# schematic_v1.net
KiCad netlist of a schematic drawn in EAGLE
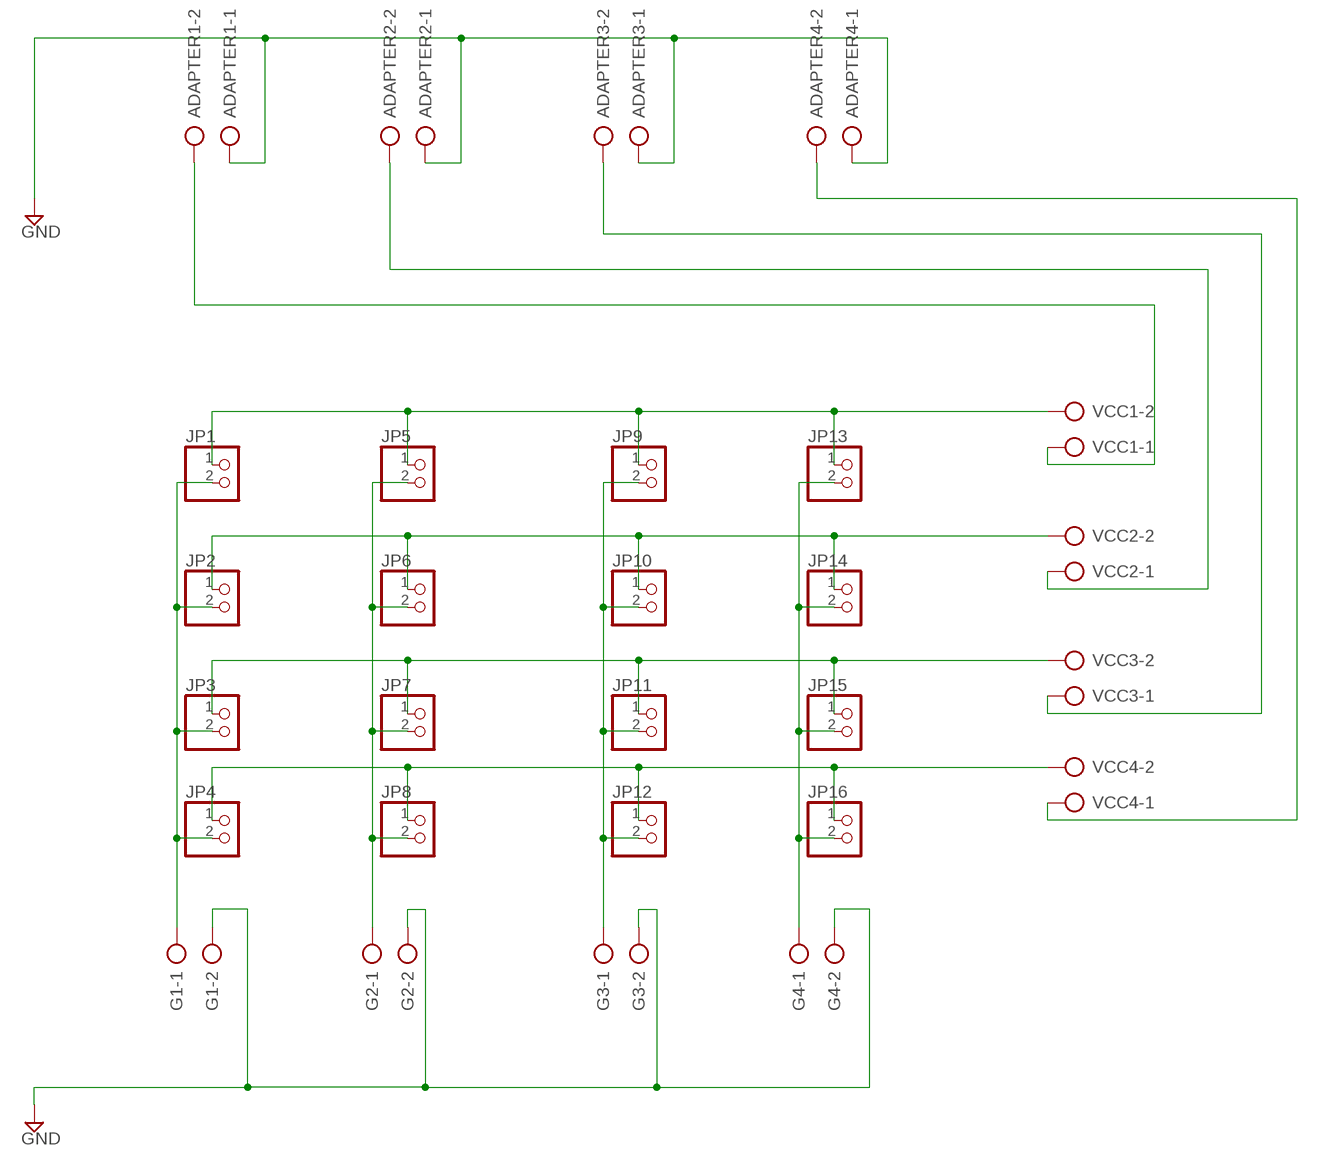
[diagram p0: schematic, sheet 1]

(export (version "E")
  (design (tool "Eeschema 10.0.6"))
  (components
    (comp (ref "ADAPTER1")
      (value "AK300/2")
      (footprint "eagle-import:AK300_2")
      (libsource (lib "eagle-import") (part "AK300/2"))
    )
    (comp (ref "ADAPTER2")
      (value "AK300/2")
      (footprint "eagle-import:AK300_2")
      (libsource (lib "eagle-import") (part "AK300/2"))
    )
    (comp (ref "ADAPTER3")
      (value "AK300/2")
      (footprint "eagle-import:AK300_2")
      (libsource (lib "eagle-import") (part "AK300/2"))
    )
    (comp (ref "ADAPTER4")
      (value "AK300/2")
      (footprint "eagle-import:AK300_2")
      (libsource (lib "eagle-import") (part "AK300/2"))
    )
    (comp (ref "G1")
      (value "AK300/2")
      (footprint "eagle-import:AK300_2")
      (libsource (lib "eagle-import") (part "AK300/2"))
    )
    (comp (ref "G2")
      (value "AK300/2")
      (footprint "eagle-import:AK300_2")
      (libsource (lib "eagle-import") (part "AK300/2"))
    )
    (comp (ref "G3")
      (value "AK300/2")
      (footprint "eagle-import:AK300_2")
      (libsource (lib "eagle-import") (part "AK300/2"))
    )
    (comp (ref "G4")
      (value "AK300/2")
      (footprint "eagle-import:AK300_2")
      (libsource (lib "eagle-import") (part "AK300/2"))
    )
    (comp (ref "JP1")
      (value "PINHD-1X2")
      (footprint "eagle-import:1X02")
      (libsource (lib "eagle-import") (part "PINHD-1X2"))
    )
    (comp (ref "JP2")
      (value "PINHD-1X2")
      (footprint "eagle-import:1X02")
      (libsource (lib "eagle-import") (part "PINHD-1X2"))
    )
    (comp (ref "JP3")
      (value "PINHD-1X2")
      (footprint "eagle-import:1X02")
      (libsource (lib "eagle-import") (part "PINHD-1X2"))
    )
    (comp (ref "JP4")
      (value "PINHD-1X2")
      (footprint "eagle-import:1X02")
      (libsource (lib "eagle-import") (part "PINHD-1X2"))
    )
    (comp (ref "JP5")
      (value "PINHD-1X2")
      (footprint "eagle-import:1X02")
      (libsource (lib "eagle-import") (part "PINHD-1X2"))
    )
    (comp (ref "JP6")
      (value "PINHD-1X2")
      (footprint "eagle-import:1X02")
      (libsource (lib "eagle-import") (part "PINHD-1X2"))
    )
    (comp (ref "JP7")
      (value "PINHD-1X2")
      (footprint "eagle-import:1X02")
      (libsource (lib "eagle-import") (part "PINHD-1X2"))
    )
    (comp (ref "JP8")
      (value "PINHD-1X2")
      (footprint "eagle-import:1X02")
      (libsource (lib "eagle-import") (part "PINHD-1X2"))
    )
    (comp (ref "JP9")
      (value "PINHD-1X2")
      (footprint "eagle-import:1X02")
      (libsource (lib "eagle-import") (part "PINHD-1X2"))
    )
    (comp (ref "JP10")
      (value "PINHD-1X2")
      (footprint "eagle-import:1X02")
      (libsource (lib "eagle-import") (part "PINHD-1X2"))
    )
    (comp (ref "JP11")
      (value "PINHD-1X2")
      (footprint "eagle-import:1X02")
      (libsource (lib "eagle-import") (part "PINHD-1X2"))
    )
    (comp (ref "JP12")
      (value "PINHD-1X2")
      (footprint "eagle-import:1X02")
      (libsource (lib "eagle-import") (part "PINHD-1X2"))
    )
    (comp (ref "JP13")
      (value "PINHD-1X2")
      (footprint "eagle-import:1X02")
      (libsource (lib "eagle-import") (part "PINHD-1X2"))
    )
    (comp (ref "JP14")
      (value "PINHD-1X2")
      (footprint "eagle-import:1X02")
      (libsource (lib "eagle-import") (part "PINHD-1X2"))
    )
    (comp (ref "JP15")
      (value "PINHD-1X2")
      (footprint "eagle-import:1X02")
      (libsource (lib "eagle-import") (part "PINHD-1X2"))
    )
    (comp (ref "JP16")
      (value "PINHD-1X2")
      (footprint "eagle-import:1X02")
      (libsource (lib "eagle-import") (part "PINHD-1X2"))
    )
    (comp (ref "VCC1")
      (value "AK300/2")
      (footprint "eagle-import:AK300_2")
      (libsource (lib "eagle-import") (part "AK300/2"))
    )
    (comp (ref "VCC2")
      (value "AK300/2")
      (footprint "eagle-import:AK300_2")
      (libsource (lib "eagle-import") (part "AK300/2"))
    )
    (comp (ref "VCC3")
      (value "AK300/2")
      (footprint "eagle-import:AK300_2")
      (libsource (lib "eagle-import") (part "AK300/2"))
    )
    (comp (ref "VCC4")
      (value "AK300/2")
      (footprint "eagle-import:AK300_2")
      (libsource (lib "eagle-import") (part "AK300/2"))
    )
  )
  (nets
    (net (code "1") (name "GND") (class "Default")
      (node (ref "ADAPTER1") (pin "1") (pinfunction "KL_1") (pintype "passive"))
      (node (ref "ADAPTER2") (pin "1") (pinfunction "KL_1") (pintype "passive"))
      (node (ref "ADAPTER3") (pin "1") (pinfunction "KL_1") (pintype "passive"))
      (node (ref "ADAPTER4") (pin "1") (pinfunction "KL_1") (pintype "passive"))
      (node (ref "G1") (pin "2") (pinfunction "KL_2") (pintype "passive"))
      (node (ref "G2") (pin "2") (pinfunction "KL_2") (pintype "passive"))
      (node (ref "G3") (pin "2") (pinfunction "KL_2") (pintype "passive"))
      (node (ref "G4") (pin "2") (pinfunction "KL_2") (pintype "passive"))
    )
    (net (code "2") (name "Net-(ADAPTER1B-KL)") (class "Default")
      (node (ref "ADAPTER1") (pin "2") (pinfunction "KL_2") (pintype "passive"))
      (node (ref "VCC1") (pin "1") (pinfunction "KL_1") (pintype "passive"))
    )
    (net (code "3") (name "Net-(ADAPTER2B-KL)") (class "Default")
      (node (ref "ADAPTER2") (pin "2") (pinfunction "KL_2") (pintype "passive"))
      (node (ref "VCC2") (pin "1") (pinfunction "KL_1") (pintype "passive"))
    )
    (net (code "4") (name "Net-(ADAPTER3B-KL)") (class "Default")
      (node (ref "ADAPTER3") (pin "2") (pinfunction "KL_2") (pintype "passive"))
      (node (ref "VCC3") (pin "1") (pinfunction "KL_1") (pintype "passive"))
    )
    (net (code "5") (name "Net-(ADAPTER4B-KL)") (class "Default")
      (node (ref "ADAPTER4") (pin "2") (pinfunction "KL_2") (pintype "passive"))
      (node (ref "VCC4") (pin "1") (pinfunction "KL_1") (pintype "passive"))
    )
    (net (code "6") (name "Net-(G1A-KL)") (class "Default")
      (node (ref "G1") (pin "1") (pinfunction "KL_1") (pintype "passive"))
      (node (ref "JP1") (pin "2") (pinfunction "2_2") (pintype "passive"))
      (node (ref "JP2") (pin "2") (pinfunction "2_2") (pintype "passive"))
      (node (ref "JP3") (pin "2") (pinfunction "2_2") (pintype "passive"))
      (node (ref "JP4") (pin "2") (pinfunction "2_2") (pintype "passive"))
    )
    (net (code "7") (name "Net-(G2A-KL)") (class "Default")
      (node (ref "G2") (pin "1") (pinfunction "KL_1") (pintype "passive"))
      (node (ref "JP5") (pin "2") (pinfunction "2_2") (pintype "passive"))
      (node (ref "JP6") (pin "2") (pinfunction "2_2") (pintype "passive"))
      (node (ref "JP7") (pin "2") (pinfunction "2_2") (pintype "passive"))
      (node (ref "JP8") (pin "2") (pinfunction "2_2") (pintype "passive"))
    )
    (net (code "8") (name "Net-(G3A-KL)") (class "Default")
      (node (ref "G3") (pin "1") (pinfunction "KL_1") (pintype "passive"))
      (node (ref "JP10") (pin "2") (pinfunction "2_2") (pintype "passive"))
      (node (ref "JP11") (pin "2") (pinfunction "2_2") (pintype "passive"))
      (node (ref "JP12") (pin "2") (pinfunction "2_2") (pintype "passive"))
      (node (ref "JP9") (pin "2") (pinfunction "2_2") (pintype "passive"))
    )
    (net (code "9") (name "Net-(G4A-KL)") (class "Default")
      (node (ref "G4") (pin "1") (pinfunction "KL_1") (pintype "passive"))
      (node (ref "JP13") (pin "2") (pinfunction "2_2") (pintype "passive"))
      (node (ref "JP14") (pin "2") (pinfunction "2_2") (pintype "passive"))
      (node (ref "JP15") (pin "2") (pinfunction "2_2") (pintype "passive"))
      (node (ref "JP16") (pin "2") (pinfunction "2_2") (pintype "passive"))
    )
    (net (code "10") (name "Net-(VCC1B-KL)") (class "Default")
      (node (ref "JP1") (pin "1") (pinfunction "1_1") (pintype "passive"))
      (node (ref "JP13") (pin "1") (pinfunction "1_1") (pintype "passive"))
      (node (ref "JP5") (pin "1") (pinfunction "1_1") (pintype "passive"))
      (node (ref "JP9") (pin "1") (pinfunction "1_1") (pintype "passive"))
      (node (ref "VCC1") (pin "2") (pinfunction "KL_2") (pintype "passive"))
    )
    (net (code "11") (name "Net-(VCC2B-KL)") (class "Default")
      (node (ref "JP10") (pin "1") (pinfunction "1_1") (pintype "passive"))
      (node (ref "JP14") (pin "1") (pinfunction "1_1") (pintype "passive"))
      (node (ref "JP2") (pin "1") (pinfunction "1_1") (pintype "passive"))
      (node (ref "JP6") (pin "1") (pinfunction "1_1") (pintype "passive"))
      (node (ref "VCC2") (pin "2") (pinfunction "KL_2") (pintype "passive"))
    )
    (net (code "12") (name "Net-(VCC3B-KL)") (class "Default")
      (node (ref "JP11") (pin "1") (pinfunction "1_1") (pintype "passive"))
      (node (ref "JP15") (pin "1") (pinfunction "1_1") (pintype "passive"))
      (node (ref "JP3") (pin "1") (pinfunction "1_1") (pintype "passive"))
      (node (ref "JP7") (pin "1") (pinfunction "1_1") (pintype "passive"))
      (node (ref "VCC3") (pin "2") (pinfunction "KL_2") (pintype "passive"))
    )
    (net (code "13") (name "Net-(VCC4B-KL)") (class "Default")
      (node (ref "JP12") (pin "1") (pinfunction "1_1") (pintype "passive"))
      (node (ref "JP16") (pin "1") (pinfunction "1_1") (pintype "passive"))
      (node (ref "JP4") (pin "1") (pinfunction "1_1") (pintype "passive"))
      (node (ref "JP8") (pin "1") (pinfunction "1_1") (pintype "passive"))
      (node (ref "VCC4") (pin "2") (pinfunction "KL_2") (pintype "passive"))
    )
  )
)
